# clouds_v302_2.net
KiCad netlist of a schematic drawn in Altium Designer
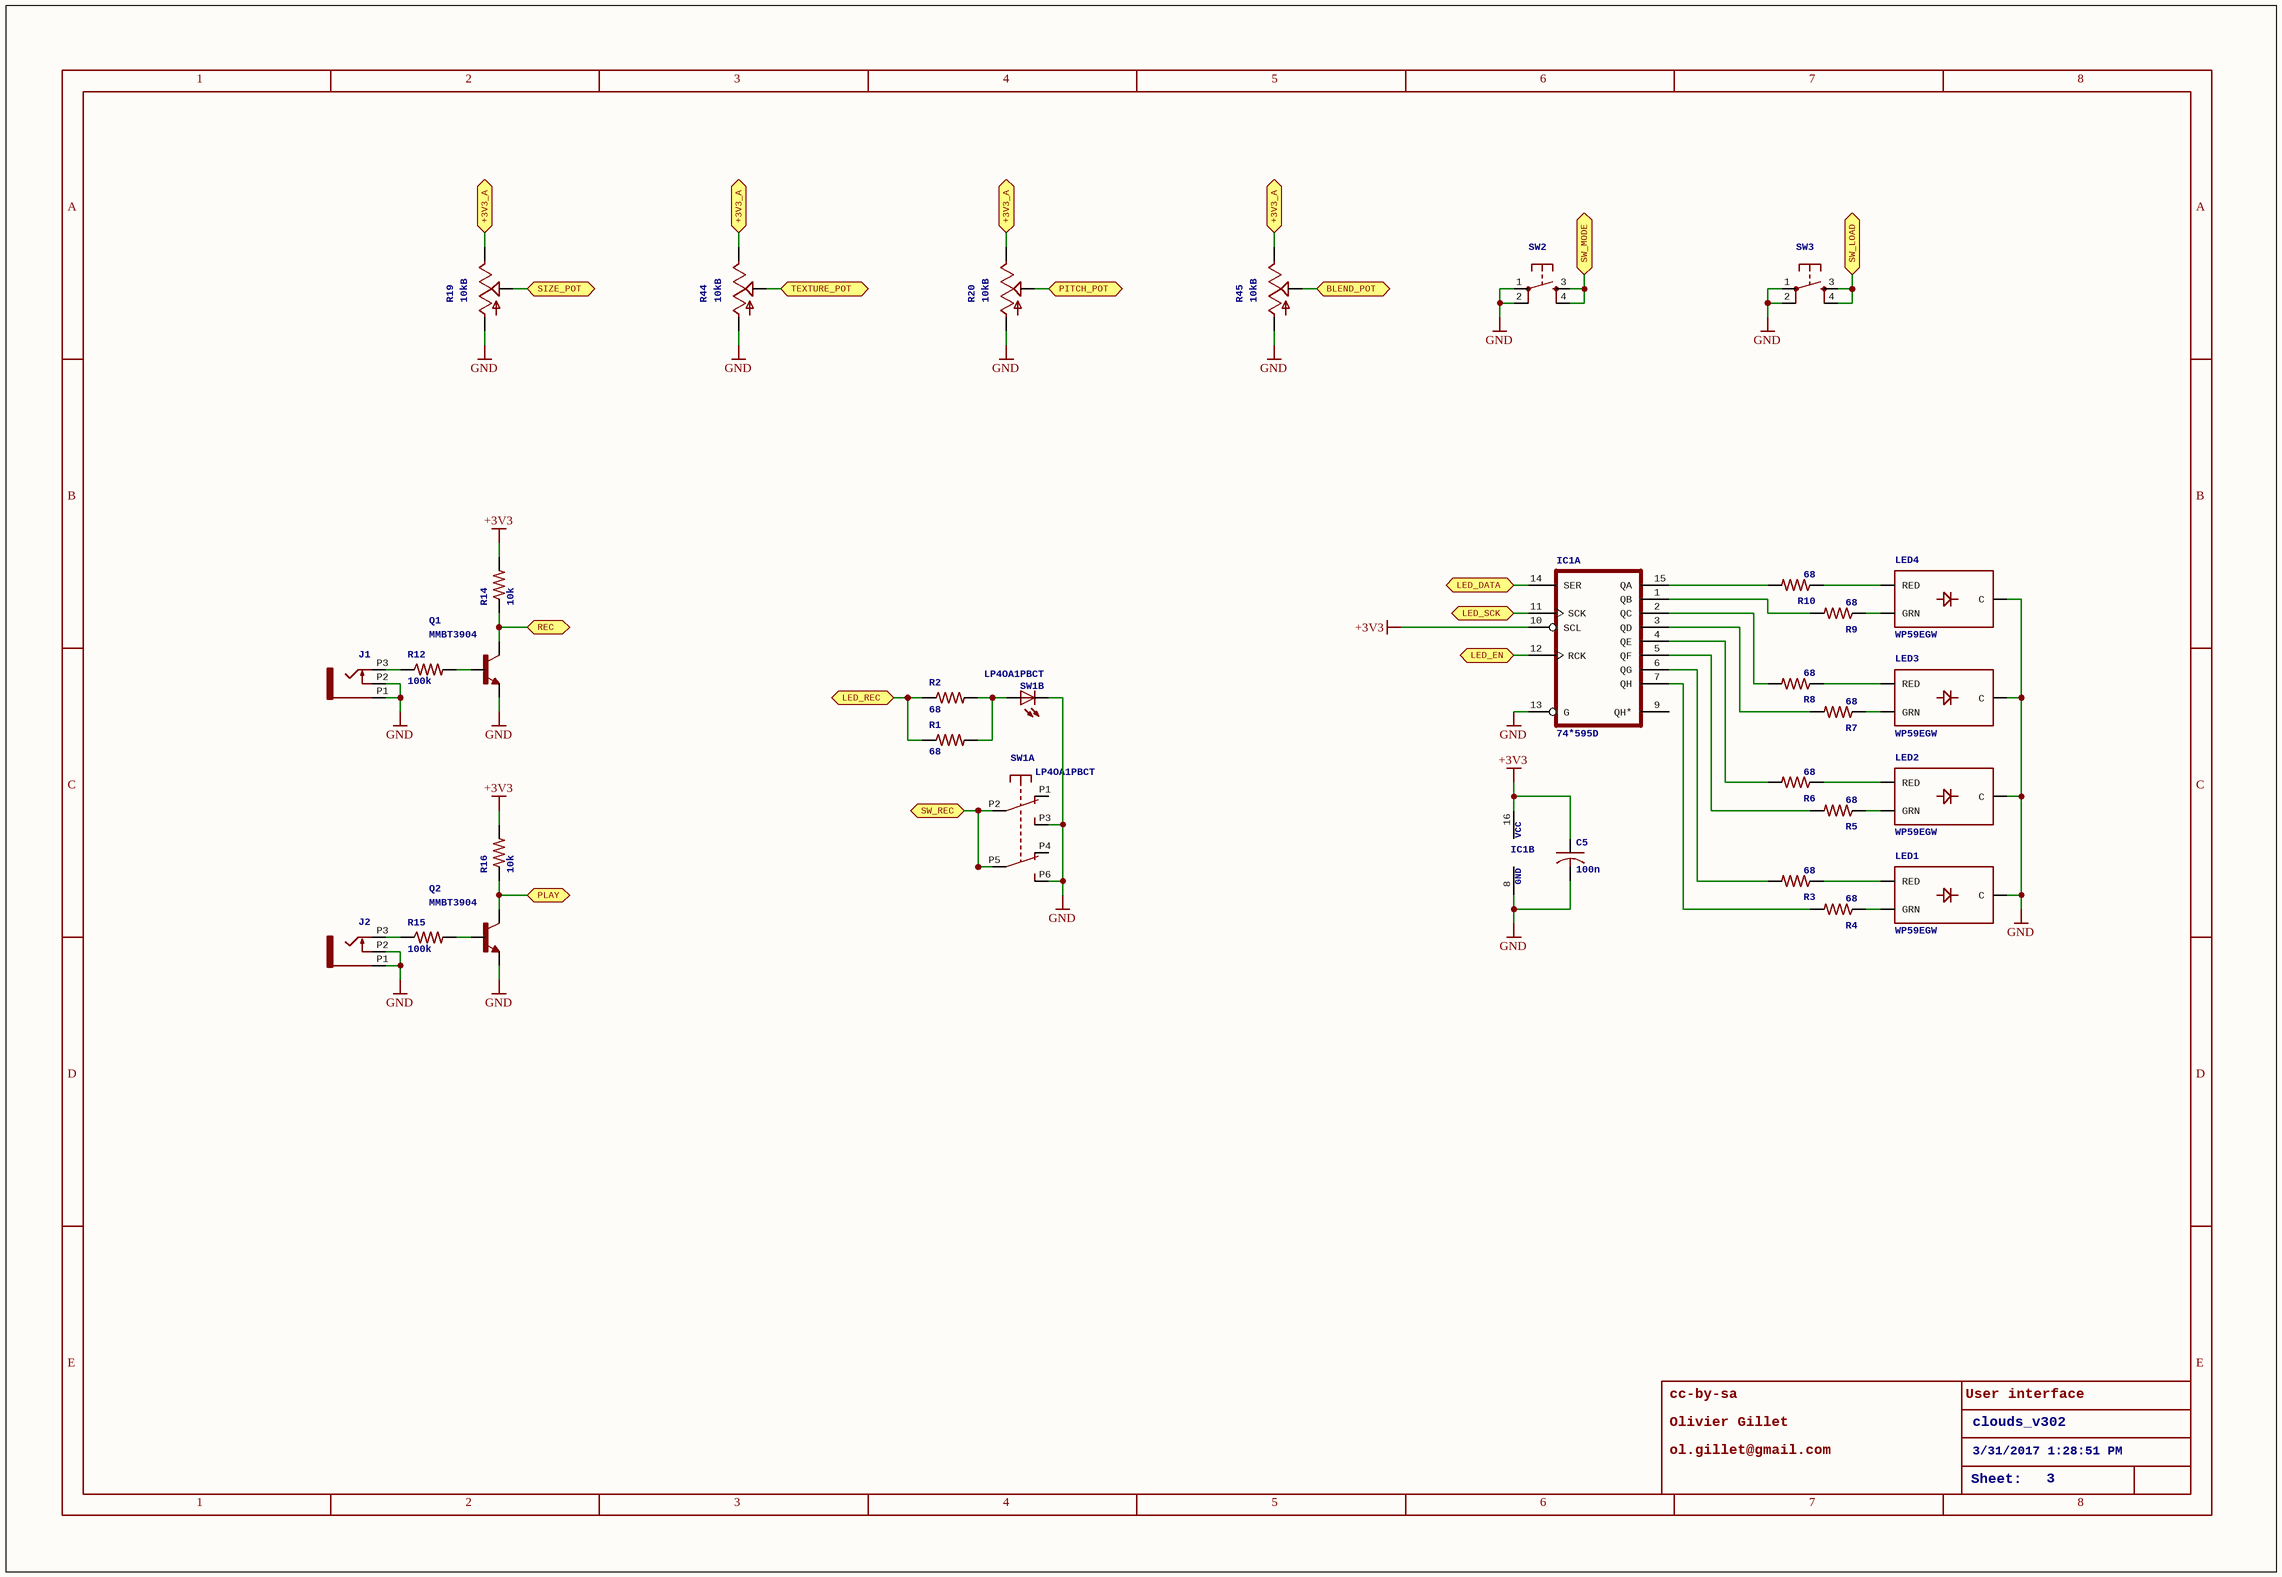
[diagram p0: clouds_v302_2.SchDoc]

(export (version "E")
  (design (tool "Eeschema 10.0.6"))
  (components
    (comp (ref "C5")
      (value "100n")
      (footprint "C0603")
      (description "CAPACITOR, American symbol")
      (libsource (lib "rcl") (part "C-USC0603"))
    )
    (comp (ref "IC1")
      (value "74*595D")
      (footprint "SO16")
      (description "8-bit SHIFT REGISTER, output latch")
      (fields (field (name "GND") "GND") (field (name "VCC") "VCC"))
      (libsource (lib "74xx-eu") (part "74*595D"))
    )
    (comp (ref "J1")
      (value "PJ301_THONKICONN6")
      (footprint "WQP_PJ_301M6")
      (libsource (lib "og-pj301") (part "PJ301_THONKICONN6"))
    )
    (comp (ref "J2")
      (value "PJ301_THONKICONN6")
      (footprint "WQP_PJ_301M6")
      (libsource (lib "og-pj301") (part "PJ301_THONKICONN6"))
    )
    (comp (ref "LED1")
      (value "WP59EGW")
      (footprint "LED-BICOLOR-THROUGHHOLE-5MM")
      (libsource (lib "og-leds") (part "LED-BICOLOR-THROUGHHOLE5MM"))
    )
    (comp (ref "LED2")
      (value "WP59EGW")
      (footprint "LED-BICOLOR-THROUGHHOLE-5MM")
      (libsource (lib "og-leds") (part "LED-BICOLOR-THROUGHHOLE5MM"))
    )
    (comp (ref "LED3")
      (value "WP59EGW")
      (footprint "LED-BICOLOR-THROUGHHOLE-5MM")
      (libsource (lib "og-leds") (part "LED-BICOLOR-THROUGHHOLE5MM"))
    )
    (comp (ref "LED4")
      (value "WP59EGW")
      (footprint "LED-BICOLOR-THROUGHHOLE-5MM")
      (libsource (lib "og-leds") (part "LED-BICOLOR-THROUGHHOLE5MM"))
    )
    (comp (ref "Q1")
      (value "MMBT3904")
      (footprint "SOT23-BEC")
      (description "NPN Transistror   BF959 corrected 2008.03.06")
      (libsource (lib "transistor") (part "*-NPN-SOT23-BEC"))
    )
    (comp (ref "Q2")
      (value "MMBT3904")
      (footprint "SOT23-BEC")
      (description "NPN Transistror   BF959 corrected 2008.03.06")
      (libsource (lib "transistor") (part "*-NPN-SOT23-BEC"))
    )
    (comp (ref "R1")
      (value "68")
      (footprint "R0603")
      (description "RESISTOR, American symbol")
      (libsource (lib "rcl") (part "R-US_R0603"))
    )
    (comp (ref "R2")
      (value "68")
      (footprint "R0603")
      (description "RESISTOR, American symbol")
      (libsource (lib "rcl") (part "R-US_R0603"))
    )
    (comp (ref "R3")
      (value "68")
      (footprint "R0603")
      (description "RESISTOR, American symbol")
      (libsource (lib "rcl") (part "R-US_R0603"))
    )
    (comp (ref "R4")
      (value "68")
      (footprint "R0603")
      (description "RESISTOR, American symbol")
      (libsource (lib "rcl") (part "R-US_R0603"))
    )
    (comp (ref "R5")
      (value "68")
      (footprint "R0603")
      (description "RESISTOR, American symbol")
      (libsource (lib "rcl") (part "R-US_R0603"))
    )
    (comp (ref "R6")
      (value "68")
      (footprint "R0603")
      (description "RESISTOR, American symbol")
      (libsource (lib "rcl") (part "R-US_R0603"))
    )
    (comp (ref "R7")
      (value "68")
      (footprint "R0603")
      (description "RESISTOR, American symbol")
      (libsource (lib "rcl") (part "R-US_R0603"))
    )
    (comp (ref "R8")
      (value "68")
      (footprint "R0603")
      (description "RESISTOR, American symbol")
      (libsource (lib "rcl") (part "R-US_R0603"))
    )
    (comp (ref "R9")
      (value "68")
      (footprint "R0603")
      (description "RESISTOR, American symbol")
      (libsource (lib "rcl") (part "R-US_R0603"))
    )
    (comp (ref "R10")
      (value "68")
      (footprint "R0603")
      (description "RESISTOR, American symbol")
      (libsource (lib "rcl") (part "R-US_R0603"))
    )
    (comp (ref "R12")
      (value "100k")
      (footprint "R0603")
      (description "RESISTOR, American symbol")
      (libsource (lib "rcl") (part "R-US_R0603"))
    )
    (comp (ref "R14")
      (value "10k")
      (footprint "R0603")
      (description "RESISTOR, American symbol")
      (libsource (lib "rcl") (part "R-US_R0603"))
    )
    (comp (ref "R15")
      (value "100k")
      (footprint "R0603")
      (description "RESISTOR, American symbol")
      (libsource (lib "rcl") (part "R-US_R0603"))
    )
    (comp (ref "R16")
      (value "10k")
      (footprint "R0603")
      (description "RESISTOR, American symbol")
      (libsource (lib "rcl") (part "R-US_R0603"))
    )
    (comp (ref "R19")
      (value "10kB")
      (footprint "ALPS_POT_VERTICAL_PS")
      (libsource (lib "og-pots") (part "POT_USVERTICAL_PS"))
    )
    (comp (ref "R20")
      (value "10kB")
      (footprint "ALPS_POT_VERTICAL_PS")
      (libsource (lib "og-pots") (part "POT_USVERTICAL_PS"))
    )
    (comp (ref "R44")
      (value "10kB")
      (footprint "ALPS_POT_VERTICAL_PS")
      (libsource (lib "og-pots") (part "POT_USVERTICAL_PS"))
    )
    (comp (ref "R45")
      (value "10kB")
      (footprint "ALPS_POT_VERTICAL_PS")
      (libsource (lib "og-pots") (part "POT_USVERTICAL_PS"))
    )
    (comp (ref "SW1")
      (value "LP4OA1PBCT")
      (footprint "LP4OA1PBCT")
      (libsource (lib "og-switch") (part "LP4OA1PBCT"))
    )
    (comp (ref "SW2")
      (value "TAC_SWITCHPTH")
      (footprint "TACTILE-PTH")
      (libsource (lib "SparkFun") (part "TAC_SWITCHPTH"))
    )
    (comp (ref "SW3")
      (value "TAC_SWITCHPTH")
      (footprint "TACTILE-PTH")
      (libsource (lib "SparkFun") (part "TAC_SWITCHPTH"))
    )
  )
  (nets
    (net (code "1") (name "+3V3") (class "Default")
      (node (ref "C5") (pin "1") (pinfunction "1_1") (pintype "passive"))
      (node (ref "IC1") (pin "10") (pinfunction "SCL_10") (pintype "passive"))
      (node (ref "IC1") (pin "16") (pinfunction "VCC_16") (pintype "power_in"))
      (node (ref "R14") (pin "2") (pinfunction "2_2") (pintype "passive"))
      (node (ref "R16") (pin "2") (pinfunction "2_2") (pintype "passive"))
    )
    (net (code "2") (name "/+3V3_A") (class "Default")
      (node (ref "R19") (pin "P$1") (pinfunction "E_P$1") (pintype "passive"))
      (node (ref "R20") (pin "P$1") (pinfunction "E_P$1") (pintype "passive"))
      (node (ref "R44") (pin "P$1") (pinfunction "E_P$1") (pintype "passive"))
      (node (ref "R45") (pin "P$1") (pinfunction "E_P$1") (pintype "passive"))
    )
    (net (code "3") (name "/BLEND_POT") (class "Default")
      (node (ref "R45") (pin "P$2") (pinfunction "S_P$2") (pintype "passive"))
    )
    (net (code "4") (name "/LED_DATA") (class "Default")
      (node (ref "IC1") (pin "14") (pinfunction "SER_14") (pintype "passive"))
    )
    (net (code "5") (name "/LED_EN") (class "Default")
      (node (ref "IC1") (pin "12") (pinfunction "RCK_12") (pintype "passive"))
    )
    (net (code "6") (name "/LED_REC") (class "Default")
      (node (ref "R1") (pin "1") (pinfunction "1_1") (pintype "passive"))
      (node (ref "R2") (pin "1") (pinfunction "1_1") (pintype "passive"))
    )
    (net (code "7") (name "/LED_SCK") (class "Default")
      (node (ref "IC1") (pin "11") (pinfunction "SCK_11") (pintype "passive"))
    )
    (net (code "8") (name "/PITCH_POT") (class "Default")
      (node (ref "R20") (pin "P$2") (pinfunction "S_P$2") (pintype "passive"))
    )
    (net (code "9") (name "/PLAY") (class "Default")
      (node (ref "Q2") (pin "C") (pinfunction "C_C") (pintype "passive"))
      (node (ref "R16") (pin "1") (pinfunction "1_1") (pintype "passive"))
    )
    (net (code "10") (name "/REC") (class "Default")
      (node (ref "Q1") (pin "C") (pinfunction "C_C") (pintype "passive"))
      (node (ref "R14") (pin "1") (pinfunction "1_1") (pintype "passive"))
    )
    (net (code "11") (name "/SIZE_POT") (class "Default")
      (node (ref "R19") (pin "P$2") (pinfunction "S_P$2") (pintype "passive"))
    )
    (net (code "12") (name "/SW_LOAD") (class "Default")
      (node (ref "SW3") (pin "3") (pinfunction "3_3") (pintype "passive"))
      (node (ref "SW3") (pin "4") (pinfunction "4_4") (pintype "passive"))
    )
    (net (code "13") (name "/SW_MODE") (class "Default")
      (node (ref "SW2") (pin "3") (pinfunction "3_3") (pintype "passive"))
      (node (ref "SW2") (pin "4") (pinfunction "4_4") (pintype "passive"))
    )
    (net (code "14") (name "/SW_REC") (class "Default")
      (node (ref "SW1") (pin "P2") (pinfunction "A2_P2") (pintype "passive"))
      (node (ref "SW1") (pin "P5") (pinfunction "B2_P5") (pintype "passive"))
    )
    (net (code "15") (name "/TEXTURE_POT") (class "Default")
      (node (ref "R44") (pin "P$2") (pinfunction "S_P$2") (pintype "passive"))
    )
    (net (code "16") (name "GND") (class "Default")
      (node (ref "C5") (pin "2") (pinfunction "2_2") (pintype "passive"))
      (node (ref "IC1") (pin "13") (pinfunction "G_13") (pintype "passive"))
      (node (ref "IC1") (pin "8") (pinfunction "GND_8") (pintype "power_in"))
      (node (ref "J1") (pin "P1") (pinfunction "1_P1") (pintype "passive"))
      (node (ref "J1") (pin "P2") (pinfunction "2_P2") (pintype "passive"))
      (node (ref "J2") (pin "P1") (pinfunction "1_P1") (pintype "passive"))
      (node (ref "J2") (pin "P2") (pinfunction "2_P2") (pintype "passive"))
      (node (ref "LED1") (pin "2") (pinfunction "C_2") (pintype "passive"))
      (node (ref "LED2") (pin "2") (pinfunction "C_2") (pintype "passive"))
      (node (ref "LED3") (pin "2") (pinfunction "C_2") (pintype "passive"))
      (node (ref "LED4") (pin "2") (pinfunction "C_2") (pintype "passive"))
      (node (ref "Q1") (pin "E") (pinfunction "E_E") (pintype "passive"))
      (node (ref "Q2") (pin "E") (pinfunction "E_E") (pintype "passive"))
      (node (ref "R19") (pin "P$3") (pinfunction "A_P$3") (pintype "passive"))
      (node (ref "R20") (pin "P$3") (pinfunction "A_P$3") (pintype "passive"))
      (node (ref "R44") (pin "P$3") (pinfunction "A_P$3") (pintype "passive"))
      (node (ref "R45") (pin "P$3") (pinfunction "A_P$3") (pintype "passive"))
      (node (ref "SW1") (pin "L2") (pinfunction "L2_L2") (pintype "passive"))
      (node (ref "SW1") (pin "P3") (pinfunction "A3_P3") (pintype "passive"))
      (node (ref "SW1") (pin "P6") (pinfunction "B3_P6") (pintype "passive"))
      (node (ref "SW2") (pin "1") (pinfunction "1_1") (pintype "passive"))
      (node (ref "SW2") (pin "2") (pinfunction "2_2") (pintype "passive"))
      (node (ref "SW3") (pin "1") (pinfunction "1_1") (pintype "passive"))
      (node (ref "SW3") (pin "2") (pinfunction "2_2") (pintype "passive"))
    )
    (net (code "17") (name "Net-(IC1A-QA)") (class "Default")
      (node (ref "IC1") (pin "15") (pinfunction "QA_15") (pintype "tri_state"))
      (node (ref "R10") (pin "2") (pinfunction "2_2") (pintype "passive"))
    )
    (net (code "18") (name "Net-(IC1A-QB)") (class "Default")
      (node (ref "IC1") (pin "1") (pinfunction "QB_1") (pintype "tri_state"))
      (node (ref "R9") (pin "2") (pinfunction "2_2") (pintype "passive"))
    )
    (net (code "19") (name "Net-(IC1A-QC)") (class "Default")
      (node (ref "IC1") (pin "2") (pinfunction "QC_2") (pintype "tri_state"))
      (node (ref "R8") (pin "2") (pinfunction "2_2") (pintype "passive"))
    )
    (net (code "20") (name "Net-(IC1A-QD)") (class "Default")
      (node (ref "IC1") (pin "3") (pinfunction "QD_3") (pintype "tri_state"))
      (node (ref "R7") (pin "2") (pinfunction "2_2") (pintype "passive"))
    )
    (net (code "21") (name "Net-(IC1A-QE)") (class "Default")
      (node (ref "IC1") (pin "4") (pinfunction "QE_4") (pintype "tri_state"))
      (node (ref "R6") (pin "2") (pinfunction "2_2") (pintype "passive"))
    )
    (net (code "22") (name "Net-(IC1A-QF)") (class "Default")
      (node (ref "IC1") (pin "5") (pinfunction "QF_5") (pintype "tri_state"))
      (node (ref "R5") (pin "2") (pinfunction "2_2") (pintype "passive"))
    )
    (net (code "23") (name "Net-(IC1A-QG)") (class "Default")
      (node (ref "IC1") (pin "6") (pinfunction "QG_6") (pintype "tri_state"))
      (node (ref "R3") (pin "2") (pinfunction "2_2") (pintype "passive"))
    )
    (net (code "24") (name "Net-(IC1A-QH)") (class "Default")
      (node (ref "IC1") (pin "7") (pinfunction "QH_7") (pintype "tri_state"))
      (node (ref "R4") (pin "2") (pinfunction "2_2") (pintype "passive"))
    )
    (net (code "25") (name "Net-(J1-3)") (class "Default")
      (node (ref "J1") (pin "P3") (pinfunction "3_P3") (pintype "passive"))
      (node (ref "R12") (pin "1") (pinfunction "1_1") (pintype "passive"))
    )
    (net (code "26") (name "Net-(J2-3)") (class "Default")
      (node (ref "J2") (pin "P3") (pinfunction "3_P3") (pintype "passive"))
      (node (ref "R15") (pin "1") (pinfunction "1_1") (pintype "passive"))
    )
    (net (code "27") (name "Net-(LED1-GRN)") (class "Default")
      (node (ref "LED1") (pin "3") (pinfunction "GRN_3") (pintype "passive"))
      (node (ref "R4") (pin "1") (pinfunction "1_1") (pintype "passive"))
    )
    (net (code "28") (name "Net-(LED1-RED)") (class "Default")
      (node (ref "LED1") (pin "1") (pinfunction "RED_1") (pintype "passive"))
      (node (ref "R3") (pin "1") (pinfunction "1_1") (pintype "passive"))
    )
    (net (code "29") (name "Net-(LED2-GRN)") (class "Default")
      (node (ref "LED2") (pin "3") (pinfunction "GRN_3") (pintype "passive"))
      (node (ref "R5") (pin "1") (pinfunction "1_1") (pintype "passive"))
    )
    (net (code "30") (name "Net-(LED2-RED)") (class "Default")
      (node (ref "LED2") (pin "1") (pinfunction "RED_1") (pintype "passive"))
      (node (ref "R6") (pin "1") (pinfunction "1_1") (pintype "passive"))
    )
    (net (code "31") (name "Net-(LED3-GRN)") (class "Default")
      (node (ref "LED3") (pin "3") (pinfunction "GRN_3") (pintype "passive"))
      (node (ref "R7") (pin "1") (pinfunction "1_1") (pintype "passive"))
    )
    (net (code "32") (name "Net-(LED3-RED)") (class "Default")
      (node (ref "LED3") (pin "1") (pinfunction "RED_1") (pintype "passive"))
      (node (ref "R8") (pin "1") (pinfunction "1_1") (pintype "passive"))
    )
    (net (code "33") (name "Net-(LED4-GRN)") (class "Default")
      (node (ref "LED4") (pin "3") (pinfunction "GRN_3") (pintype "passive"))
      (node (ref "R9") (pin "1") (pinfunction "1_1") (pintype "passive"))
    )
    (net (code "34") (name "Net-(LED4-RED)") (class "Default")
      (node (ref "LED4") (pin "1") (pinfunction "RED_1") (pintype "passive"))
      (node (ref "R10") (pin "1") (pinfunction "1_1") (pintype "passive"))
    )
    (net (code "35") (name "Net-(Q1-PadB)") (class "Default")
      (node (ref "Q1") (pin "B") (pinfunction "B_B") (pintype "passive"))
      (node (ref "R12") (pin "2") (pinfunction "2_2") (pintype "passive"))
    )
    (net (code "36") (name "Net-(Q2-PadB)") (class "Default")
      (node (ref "Q2") (pin "B") (pinfunction "B_B") (pintype "passive"))
      (node (ref "R15") (pin "2") (pinfunction "2_2") (pintype "passive"))
    )
    (net (code "37") (name "Net-(R1-Pad2)") (class "Default")
      (node (ref "R1") (pin "2") (pinfunction "2_2") (pintype "passive"))
      (node (ref "R2") (pin "2") (pinfunction "2_2") (pintype "passive"))
      (node (ref "SW1") (pin "L1") (pinfunction "L1_L1") (pintype "passive"))
    )
    (net (code "38") (name "unconnected-(IC1A-QH*-Pad9)") (class "Default")
      (node (ref "IC1") (pin "9") (pinfunction "QH*_9") (pintype "tri_state"))
    )
    (net (code "39") (name "unconnected-(SW1A-A1-PadP1)") (class "Default")
      (node (ref "SW1") (pin "P1") (pinfunction "A1_P1") (pintype "passive"))
    )
    (net (code "40") (name "unconnected-(SW1A-B1-PadP4)") (class "Default")
      (node (ref "SW1") (pin "P4") (pinfunction "B1_P4") (pintype "passive"))
    )
  )
)
